# 19-CPLD.net
KiCad netlist of a schematic drawn in Altium Designer
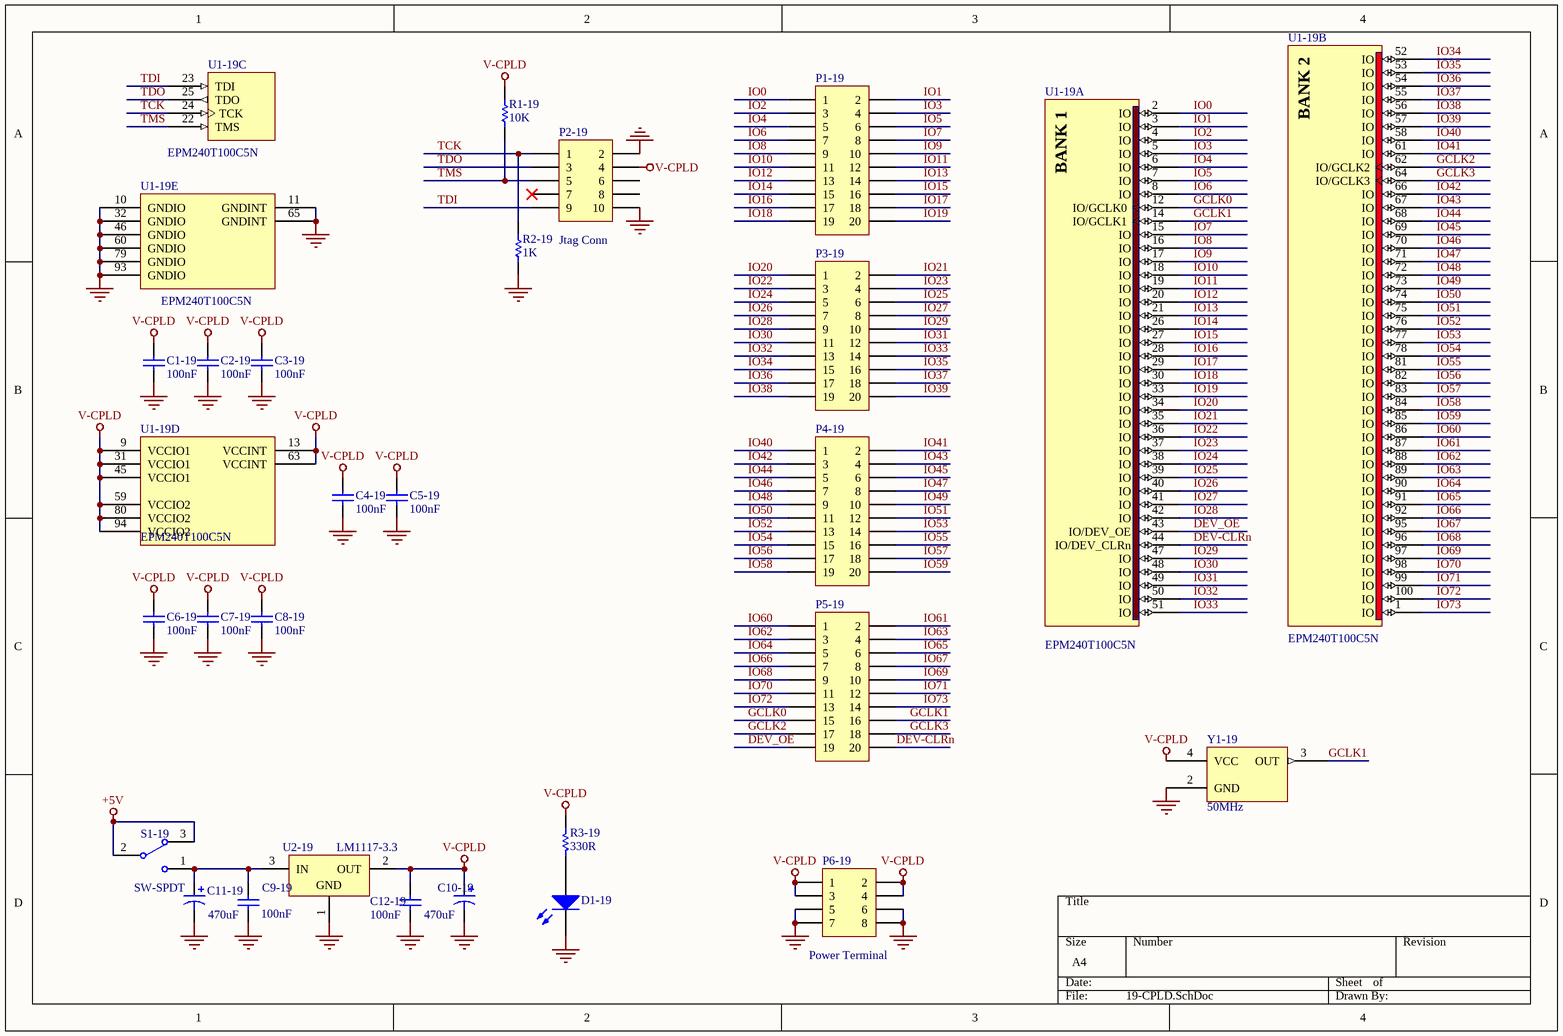
[diagram p0: 19-CPLD.SchDoc]

(export (version "E")
  (design (tool "Eeschema 10.0.6"))
  (components
    (comp (ref "C1-19")
      (value "100nF")
      (footprint "c-0805")
      (description "Capacitor")
      (fields (field (name "Comment") "104") (field (name "PUBLISHER") "Altium Limited"))
      (libsource (lib "Miscellaneous Devices") (part "Cap"))
    )
    (comp (ref "C2-19")
      (value "100nF")
      (footprint "c-0805")
      (description "Capacitor")
      (fields (field (name "Comment") "104") (field (name "PUBLISHER") "Altium Limited"))
      (libsource (lib "Miscellaneous Devices") (part "Cap"))
    )
    (comp (ref "C3-19")
      (value "100nF")
      (footprint "c-0805")
      (description "Capacitor")
      (fields (field (name "Comment") "104") (field (name "PUBLISHER") "Altium Limited"))
      (libsource (lib "Miscellaneous Devices") (part "Cap"))
    )
    (comp (ref "C4-19")
      (value "100nF")
      (footprint "c-0805")
      (description "Capacitor")
      (fields (field (name "Comment") "104") (field (name "PUBLISHER") "Altium Limited"))
      (libsource (lib "Miscellaneous Devices") (part "Cap"))
    )
    (comp (ref "C5-19")
      (value "100nF")
      (footprint "c-0805")
      (description "Capacitor")
      (fields (field (name "Comment") "104") (field (name "PUBLISHER") "Altium Limited"))
      (libsource (lib "Miscellaneous Devices") (part "Cap"))
    )
    (comp (ref "C6-19")
      (value "100nF")
      (footprint "c-0805")
      (description "Capacitor")
      (fields (field (name "Comment") "104") (field (name "PUBLISHER") "Altium Limited"))
      (libsource (lib "Miscellaneous Devices") (part "Cap"))
    )
    (comp (ref "C7-19")
      (value "100nF")
      (footprint "c-0805")
      (description "Capacitor")
      (fields (field (name "Comment") "104") (field (name "PUBLISHER") "Altium Limited"))
      (libsource (lib "Miscellaneous Devices") (part "Cap"))
    )
    (comp (ref "C8-19")
      (value "100nF")
      (footprint "c-0805")
      (description "Capacitor")
      (fields (field (name "Comment") "104") (field (name "PUBLISHER") "Altium Limited"))
      (libsource (lib "Miscellaneous Devices") (part "Cap"))
    )
    (comp (ref "C9-19")
      (value "100nF")
      (footprint "c-0805")
      (description "Capacitor")
      (fields
        (field (name "MANUFACTURER") "Generic Components")
        (field (name "Comment") "104")
        (field (name "PUBLISHER") "Altium Hobart Technology Centre")
      )
      (libsource (lib "Miscellaneous Devices") (part "Cap"))
    )
    (comp (ref "C10-19")
      (value "470uF")
      (footprint "C-ALU-10x10mm")
      (description "Polarized Capacitor (Radial)")
      (fields (field (name "Comment") "470uF/16V") (field (name "PUBLISHER") "Altium Limited"))
      (libsource (lib "Miscellaneous Devices") (part "Cap Pol1"))
    )
    (comp (ref "C11-19")
      (value "470uF")
      (footprint "C-ALU-10x10mm")
      (description "Polarized Capacitor (Radial)")
      (fields (field (name "Comment") "470uF/16V") (field (name "PUBLISHER") "Altium Limited"))
      (libsource (lib "Miscellaneous Devices") (part "Cap Pol1"))
    )
    (comp (ref "C12-19")
      (value "100nF")
      (footprint "c-0805")
      (description "Capacitor")
      (fields
        (field (name "MANUFACTURER") "Generic Components")
        (field (name "Comment") "104")
        (field (name "PUBLISHER") "Altium Hobart Technology Centre")
      )
      (libsource (lib "Miscellaneous Devices") (part "Cap"))
    )
    (comp (ref "D1-19")
      (value "LED")
      (footprint "LED-0805")
      (description "Typical INFRARED GaAs LED")
      (fields (field (name "PUBLISHER") "Altium Limited"))
      (libsource (lib "Miscellaneous Devices") (part "LED0"))
    )
    (comp (ref "P1-19")
      (value "H2")
      (footprint "HDR2X10")
      (description "Header, 10-Pin, Dual row")
      (libsource (lib "Miscellaneous Connectors") (part "Header 10X2"))
    )
    (comp (ref "P2-19")
      (value "Jtag Conn")
      (footprint "CONN-IDC-5X2-A")
      (description "Header, 5-Pin, Dual row")
      (fields (field (name "Comment") "IDE5x2"))
      (libsource (lib "Miscellaneous Connectors") (part "Header 5X2"))
    )
    (comp (ref "P3-19")
      (value "H2")
      (footprint "HDR2X10")
      (description "Header, 10-Pin, Dual row")
      (libsource (lib "Miscellaneous Connectors") (part "Header 10X2"))
    )
    (comp (ref "P4-19")
      (value "H2")
      (footprint "HDR2X10")
      (description "Header, 10-Pin, Dual row")
      (libsource (lib "Miscellaneous Connectors") (part "Header 10X2"))
    )
    (comp (ref "P5-19")
      (value "H2")
      (footprint "HDR2X10")
      (description "Header, 10-Pin, Dual row")
      (libsource (lib "Miscellaneous Connectors") (part "Header 10X2"))
    )
    (comp (ref "P6-19")
      (value "Header 4X2")
      (footprint "JP2.54-F-2x04A")
      (description "Header, 4-Pin, Dual row")
      (fields (field (name "PUBLISHER") "Power Terminal"))
      (libsource (lib "Miscellaneous Connectors") (part "Header 4X2"))
    )
    (comp (ref "R1-19")
      (value "10K")
      (footprint "R-0805")
      (description "Resistor")
      (fields (field (name "PUBLISHER") "Altium Limited"))
      (libsource (lib "Miscellaneous Devices") (part "Res1"))
    )
    (comp (ref "R2-19")
      (value "1K")
      (footprint "R-0805")
      (description "Resistor")
      (fields (field (name "PUBLISHER") "Altium Limited"))
      (libsource (lib "Miscellaneous Devices") (part "Res1"))
    )
    (comp (ref "R3-19")
      (value "330R")
      (footprint "R-0805")
      (description "Resistor")
      (fields (field (name "Comment") "331") (field (name "PUBLISHER") "Altium Limited"))
      (libsource (lib "") (part "Res1_1"))
    )
    (comp (ref "S1-19")
      (value "SW-SPDT")
      (footprint "SW-SLIDE-2P-2W")
      (description "SPDT Subminiature Toggle Switch, Right Angle Mounting, Vertical Actuation")
      (fields (field (name "PUBLISHER") "Altium Limited"))
      (libsource (lib "Miscellaneous Devices") (part "SW-SPDT"))
    )
    (comp (ref "U1-19")
      (value "EPM240T100C5N")
      (footprint "TQFP-100")
      (fields (field (name "PUBLISHER") "Altium Limited"))
      (libsource (lib "Altera MAX II") (part "EPM240T100C5N"))
    )
    (comp (ref "U2-19")
      (value "LM1117-3.3")
      (footprint "SOT-223-3")
      (description "800mA Low-Dropout Linear Regulator, 3-pin TO-252")
      (fields
        (field (name "PARTNUMBER") "LM1117IDTX-3.3")
        (field (name "MANUFACTURER") "National Semiconductor")
        (field (name "PUBLISHER") "Altium Limited")
      )
      (libsource (lib "NSC LDO") (part "LM1117IDTX-3.3"))
    )
    (comp (ref "Y1-19")
      (value "50MHz")
      (footprint "XTAL-SMD5070")
      (description "XTAL 50MHz, 4pin")
      (libsource (lib "Dlib") (part "OSC"))
    )
  )
  (nets
    (net (code "1") (name "+5V") (class "Default")
      (node (ref "S1-19") (pin "2") (pinfunction "2_2") (pintype "passive"))
      (node (ref "S1-19") (pin "3") (pinfunction "3_3") (pintype "passive"))
    )
    (net (code "2") (name "/DEV-CLRn") (class "Default")
      (node (ref "P5-19") (pin "20") (pinfunction "20_20") (pintype "passive"))
      (node (ref "U1-19") (pin "44") (pinfunction "IO/DEV_CLRn_44") (pintype "bidirectional"))
    )
    (net (code "3") (name "/DEV_OE") (class "Default")
      (node (ref "P5-19") (pin "19") (pinfunction "19_19") (pintype "passive"))
      (node (ref "U1-19") (pin "43") (pinfunction "IO/DEV_OE_43") (pintype "bidirectional"))
    )
    (net (code "4") (name "/GCLK0") (class "Default")
      (node (ref "P5-19") (pin "15") (pinfunction "15_15") (pintype "passive"))
      (node (ref "U1-19") (pin "12") (pinfunction "IO/GCLK0_12") (pintype "bidirectional"))
    )
    (net (code "5") (name "/GCLK1") (class "Default")
      (node (ref "P5-19") (pin "16") (pinfunction "16_16") (pintype "passive"))
      (node (ref "U1-19") (pin "14") (pinfunction "IO/GCLK1_14") (pintype "bidirectional"))
      (node (ref "Y1-19") (pin "3") (pinfunction "OUT_3") (pintype "output"))
    )
    (net (code "6") (name "/GCLK2") (class "Default")
      (node (ref "P5-19") (pin "17") (pinfunction "17_17") (pintype "passive"))
      (node (ref "U1-19") (pin "62") (pinfunction "IO/GCLK2_62") (pintype "bidirectional"))
    )
    (net (code "7") (name "/GCLK3") (class "Default")
      (node (ref "P5-19") (pin "18") (pinfunction "18_18") (pintype "passive"))
      (node (ref "U1-19") (pin "64") (pinfunction "IO/GCLK3_64") (pintype "bidirectional"))
    )
    (net (code "8") (name "/IO0") (class "Default")
      (node (ref "P1-19") (pin "1") (pinfunction "1_1") (pintype "passive"))
      (node (ref "U1-19") (pin "2") (pinfunction "IO_2") (pintype "bidirectional"))
    )
    (net (code "9") (name "/IO1") (class "Default")
      (node (ref "P1-19") (pin "2") (pinfunction "2_2") (pintype "passive"))
      (node (ref "U1-19") (pin "3") (pinfunction "IO_3") (pintype "bidirectional"))
    )
    (net (code "10") (name "/IO2") (class "Default")
      (node (ref "P1-19") (pin "3") (pinfunction "3_3") (pintype "passive"))
      (node (ref "U1-19") (pin "4") (pinfunction "IO_4") (pintype "bidirectional"))
    )
    (net (code "11") (name "/IO3") (class "Default")
      (node (ref "P1-19") (pin "4") (pinfunction "4_4") (pintype "passive"))
      (node (ref "U1-19") (pin "5") (pinfunction "IO_5") (pintype "bidirectional"))
    )
    (net (code "12") (name "/IO4") (class "Default")
      (node (ref "P1-19") (pin "5") (pinfunction "5_5") (pintype "passive"))
      (node (ref "U1-19") (pin "6") (pinfunction "IO_6") (pintype "bidirectional"))
    )
    (net (code "13") (name "/IO5") (class "Default")
      (node (ref "P1-19") (pin "6") (pinfunction "6_6") (pintype "passive"))
      (node (ref "U1-19") (pin "7") (pinfunction "IO_7") (pintype "bidirectional"))
    )
    (net (code "14") (name "/IO6") (class "Default")
      (node (ref "P1-19") (pin "7") (pinfunction "7_7") (pintype "passive"))
      (node (ref "U1-19") (pin "8") (pinfunction "IO_8") (pintype "bidirectional"))
    )
    (net (code "15") (name "/IO7") (class "Default")
      (node (ref "P1-19") (pin "8") (pinfunction "8_8") (pintype "passive"))
      (node (ref "U1-19") (pin "15") (pinfunction "IO_15") (pintype "bidirectional"))
    )
    (net (code "16") (name "/IO8") (class "Default")
      (node (ref "P1-19") (pin "9") (pinfunction "9_9") (pintype "passive"))
      (node (ref "U1-19") (pin "16") (pinfunction "IO_16") (pintype "bidirectional"))
    )
    (net (code "17") (name "/IO9") (class "Default")
      (node (ref "P1-19") (pin "10") (pinfunction "10_10") (pintype "passive"))
      (node (ref "U1-19") (pin "17") (pinfunction "IO_17") (pintype "bidirectional"))
    )
    (net (code "18") (name "/IO10") (class "Default")
      (node (ref "P1-19") (pin "11") (pinfunction "11_11") (pintype "passive"))
      (node (ref "U1-19") (pin "18") (pinfunction "IO_18") (pintype "bidirectional"))
    )
    (net (code "19") (name "/IO11") (class "Default")
      (node (ref "P1-19") (pin "12") (pinfunction "12_12") (pintype "passive"))
      (node (ref "U1-19") (pin "19") (pinfunction "IO_19") (pintype "bidirectional"))
    )
    (net (code "20") (name "/IO12") (class "Default")
      (node (ref "P1-19") (pin "13") (pinfunction "13_13") (pintype "passive"))
      (node (ref "U1-19") (pin "20") (pinfunction "IO_20") (pintype "bidirectional"))
    )
    (net (code "21") (name "/IO13") (class "Default")
      (node (ref "P1-19") (pin "14") (pinfunction "14_14") (pintype "passive"))
      (node (ref "U1-19") (pin "21") (pinfunction "IO_21") (pintype "bidirectional"))
    )
    (net (code "22") (name "/IO14") (class "Default")
      (node (ref "P1-19") (pin "15") (pinfunction "15_15") (pintype "passive"))
      (node (ref "U1-19") (pin "26") (pinfunction "IO_26") (pintype "bidirectional"))
    )
    (net (code "23") (name "/IO15") (class "Default")
      (node (ref "P1-19") (pin "16") (pinfunction "16_16") (pintype "passive"))
      (node (ref "U1-19") (pin "27") (pinfunction "IO_27") (pintype "bidirectional"))
    )
    (net (code "24") (name "/IO16") (class "Default")
      (node (ref "P1-19") (pin "17") (pinfunction "17_17") (pintype "passive"))
      (node (ref "U1-19") (pin "28") (pinfunction "IO_28") (pintype "bidirectional"))
    )
    (net (code "25") (name "/IO17") (class "Default")
      (node (ref "P1-19") (pin "18") (pinfunction "18_18") (pintype "passive"))
      (node (ref "U1-19") (pin "29") (pinfunction "IO_29") (pintype "bidirectional"))
    )
    (net (code "26") (name "/IO18") (class "Default")
      (node (ref "P1-19") (pin "19") (pinfunction "19_19") (pintype "passive"))
      (node (ref "U1-19") (pin "30") (pinfunction "IO_30") (pintype "bidirectional"))
    )
    (net (code "27") (name "/IO19") (class "Default")
      (node (ref "P1-19") (pin "20") (pinfunction "20_20") (pintype "passive"))
      (node (ref "U1-19") (pin "33") (pinfunction "IO_33") (pintype "bidirectional"))
    )
    (net (code "28") (name "/IO20") (class "Default")
      (node (ref "P3-19") (pin "1") (pinfunction "1_1") (pintype "passive"))
      (node (ref "U1-19") (pin "34") (pinfunction "IO_34") (pintype "bidirectional"))
    )
    (net (code "29") (name "/IO21") (class "Default")
      (node (ref "P3-19") (pin "2") (pinfunction "2_2") (pintype "passive"))
      (node (ref "U1-19") (pin "35") (pinfunction "IO_35") (pintype "bidirectional"))
    )
    (net (code "30") (name "/IO22") (class "Default")
      (node (ref "P3-19") (pin "3") (pinfunction "3_3") (pintype "passive"))
      (node (ref "U1-19") (pin "36") (pinfunction "IO_36") (pintype "bidirectional"))
    )
    (net (code "31") (name "/IO23") (class "Default")
      (node (ref "P3-19") (pin "4") (pinfunction "4_4") (pintype "passive"))
      (node (ref "U1-19") (pin "37") (pinfunction "IO_37") (pintype "bidirectional"))
    )
    (net (code "32") (name "/IO24") (class "Default")
      (node (ref "P3-19") (pin "5") (pinfunction "5_5") (pintype "passive"))
      (node (ref "U1-19") (pin "38") (pinfunction "IO_38") (pintype "bidirectional"))
    )
    (net (code "33") (name "/IO25") (class "Default")
      (node (ref "P3-19") (pin "6") (pinfunction "6_6") (pintype "passive"))
      (node (ref "U1-19") (pin "39") (pinfunction "IO_39") (pintype "bidirectional"))
    )
    (net (code "34") (name "/IO26") (class "Default")
      (node (ref "P3-19") (pin "7") (pinfunction "7_7") (pintype "passive"))
      (node (ref "U1-19") (pin "40") (pinfunction "IO_40") (pintype "bidirectional"))
    )
    (net (code "35") (name "/IO27") (class "Default")
      (node (ref "P3-19") (pin "8") (pinfunction "8_8") (pintype "passive"))
      (node (ref "U1-19") (pin "41") (pinfunction "IO_41") (pintype "bidirectional"))
    )
    (net (code "36") (name "/IO28") (class "Default")
      (node (ref "P3-19") (pin "9") (pinfunction "9_9") (pintype "passive"))
      (node (ref "U1-19") (pin "42") (pinfunction "IO_42") (pintype "bidirectional"))
    )
    (net (code "37") (name "/IO29") (class "Default")
      (node (ref "P3-19") (pin "10") (pinfunction "10_10") (pintype "passive"))
      (node (ref "U1-19") (pin "47") (pinfunction "IO_47") (pintype "bidirectional"))
    )
    (net (code "38") (name "/IO30") (class "Default")
      (node (ref "P3-19") (pin "11") (pinfunction "11_11") (pintype "passive"))
      (node (ref "U1-19") (pin "48") (pinfunction "IO_48") (pintype "bidirectional"))
    )
    (net (code "39") (name "/IO31") (class "Default")
      (node (ref "P3-19") (pin "12") (pinfunction "12_12") (pintype "passive"))
      (node (ref "U1-19") (pin "49") (pinfunction "IO_49") (pintype "bidirectional"))
    )
    (net (code "40") (name "/IO32") (class "Default")
      (node (ref "P3-19") (pin "13") (pinfunction "13_13") (pintype "passive"))
      (node (ref "U1-19") (pin "50") (pinfunction "IO_50") (pintype "bidirectional"))
    )
    (net (code "41") (name "/IO33") (class "Default")
      (node (ref "P3-19") (pin "14") (pinfunction "14_14") (pintype "passive"))
      (node (ref "U1-19") (pin "51") (pinfunction "IO_51") (pintype "bidirectional"))
    )
    (net (code "42") (name "/IO34") (class "Default")
      (node (ref "P3-19") (pin "15") (pinfunction "15_15") (pintype "passive"))
      (node (ref "U1-19") (pin "52") (pinfunction "IO_52") (pintype "bidirectional"))
    )
    (net (code "43") (name "/IO35") (class "Default")
      (node (ref "P3-19") (pin "16") (pinfunction "16_16") (pintype "passive"))
      (node (ref "U1-19") (pin "53") (pinfunction "IO_53") (pintype "bidirectional"))
    )
    (net (code "44") (name "/IO36") (class "Default")
      (node (ref "P3-19") (pin "17") (pinfunction "17_17") (pintype "passive"))
      (node (ref "U1-19") (pin "54") (pinfunction "IO_54") (pintype "bidirectional"))
    )
    (net (code "45") (name "/IO37") (class "Default")
      (node (ref "P3-19") (pin "18") (pinfunction "18_18") (pintype "passive"))
      (node (ref "U1-19") (pin "55") (pinfunction "IO_55") (pintype "bidirectional"))
    )
    (net (code "46") (name "/IO38") (class "Default")
      (node (ref "P3-19") (pin "19") (pinfunction "19_19") (pintype "passive"))
      (node (ref "U1-19") (pin "56") (pinfunction "IO_56") (pintype "bidirectional"))
    )
    (net (code "47") (name "/IO39") (class "Default")
      (node (ref "P3-19") (pin "20") (pinfunction "20_20") (pintype "passive"))
      (node (ref "U1-19") (pin "57") (pinfunction "IO_57") (pintype "bidirectional"))
    )
    (net (code "48") (name "/IO40") (class "Default")
      (node (ref "P4-19") (pin "1") (pinfunction "1_1") (pintype "passive"))
      (node (ref "U1-19") (pin "58") (pinfunction "IO_58") (pintype "bidirectional"))
    )
    (net (code "49") (name "/IO41") (class "Default")
      (node (ref "P4-19") (pin "2") (pinfunction "2_2") (pintype "passive"))
      (node (ref "U1-19") (pin "61") (pinfunction "IO_61") (pintype "bidirectional"))
    )
    (net (code "50") (name "/IO42") (class "Default")
      (node (ref "P4-19") (pin "3") (pinfunction "3_3") (pintype "passive"))
      (node (ref "U1-19") (pin "66") (pinfunction "IO_66") (pintype "bidirectional"))
    )
    (net (code "51") (name "/IO43") (class "Default")
      (node (ref "P4-19") (pin "4") (pinfunction "4_4") (pintype "passive"))
      (node (ref "U1-19") (pin "67") (pinfunction "IO_67") (pintype "bidirectional"))
    )
    (net (code "52") (name "/IO44") (class "Default")
      (node (ref "P4-19") (pin "5") (pinfunction "5_5") (pintype "passive"))
      (node (ref "U1-19") (pin "68") (pinfunction "IO_68") (pintype "bidirectional"))
    )
    (net (code "53") (name "/IO45") (class "Default")
      (node (ref "P4-19") (pin "6") (pinfunction "6_6") (pintype "passive"))
      (node (ref "U1-19") (pin "69") (pinfunction "IO_69") (pintype "bidirectional"))
    )
    (net (code "54") (name "/IO46") (class "Default")
      (node (ref "P4-19") (pin "7") (pinfunction "7_7") (pintype "passive"))
      (node (ref "U1-19") (pin "70") (pinfunction "IO_70") (pintype "bidirectional"))
    )
    (net (code "55") (name "/IO47") (class "Default")
      (node (ref "P4-19") (pin "8") (pinfunction "8_8") (pintype "passive"))
      (node (ref "U1-19") (pin "71") (pinfunction "IO_71") (pintype "bidirectional"))
    )
    (net (code "56") (name "/IO48") (class "Default")
      (node (ref "P4-19") (pin "9") (pinfunction "9_9") (pintype "passive"))
      (node (ref "U1-19") (pin "72") (pinfunction "IO_72") (pintype "bidirectional"))
    )
    (net (code "57") (name "/IO49") (class "Default")
      (node (ref "P4-19") (pin "10") (pinfunction "10_10") (pintype "passive"))
      (node (ref "U1-19") (pin "73") (pinfunction "IO_73") (pintype "bidirectional"))
    )
    (net (code "58") (name "/IO50") (class "Default")
      (node (ref "P4-19") (pin "11") (pinfunction "11_11") (pintype "passive"))
      (node (ref "U1-19") (pin "74") (pinfunction "IO_74") (pintype "bidirectional"))
    )
    (net (code "59") (name "/IO51") (class "Default")
      (node (ref "P4-19") (pin "12") (pinfunction "12_12") (pintype "passive"))
      (node (ref "U1-19") (pin "75") (pinfunction "IO_75") (pintype "bidirectional"))
    )
    (net (code "60") (name "/IO52") (class "Default")
      (node (ref "P4-19") (pin "13") (pinfunction "13_13") (pintype "passive"))
      (node (ref "U1-19") (pin "76") (pinfunction "IO_76") (pintype "bidirectional"))
    )
    (net (code "61") (name "/IO53") (class "Default")
      (node (ref "P4-19") (pin "14") (pinfunction "14_14") (pintype "passive"))
      (node (ref "U1-19") (pin "77") (pinfunction "IO_77") (pintype "bidirectional"))
    )
    (net (code "62") (name "/IO54") (class "Default")
      (node (ref "P4-19") (pin "15") (pinfunction "15_15") (pintype "passive"))
      (node (ref "U1-19") (pin "78") (pinfunction "IO_78") (pintype "bidirectional"))
    )
    (net (code "63") (name "/IO55") (class "Default")
      (node (ref "P4-19") (pin "16") (pinfunction "16_16") (pintype "passive"))
      (node (ref "U1-19") (pin "81") (pinfunction "IO_81") (pintype "bidirectional"))
    )
    (net (code "64") (name "/IO56") (class "Default")
      (node (ref "P4-19") (pin "17") (pinfunction "17_17") (pintype "passive"))
      (node (ref "U1-19") (pin "82") (pinfunction "IO_82") (pintype "bidirectional"))
    )
    (net (code "65") (name "/IO57") (class "Default")
      (node (ref "P4-19") (pin "18") (pinfunction "18_18") (pintype "passive"))
      (node (ref "U1-19") (pin "83") (pinfunction "IO_83") (pintype "bidirectional"))
    )
    (net (code "66") (name "/IO58") (class "Default")
      (node (ref "P4-19") (pin "19") (pinfunction "19_19") (pintype "passive"))
      (node (ref "U1-19") (pin "84") (pinfunction "IO_84") (pintype "bidirectional"))
    )
    (net (code "67") (name "/IO59") (class "Default")
      (node (ref "P4-19") (pin "20") (pinfunction "20_20") (pintype "passive"))
      (node (ref "U1-19") (pin "85") (pinfunction "IO_85") (pintype "bidirectional"))
    )
    (net (code "68") (name "/IO60") (class "Default")
      (node (ref "P5-19") (pin "1") (pinfunction "1_1") (pintype "passive"))
      (node (ref "U1-19") (pin "86") (pinfunction "IO_86") (pintype "bidirectional"))
    )
    (net (code "69") (name "/IO61") (class "Default")
      (node (ref "P5-19") (pin "2") (pinfunction "2_2") (pintype "passive"))
      (node (ref "U1-19") (pin "87") (pinfunction "IO_87") (pintype "bidirectional"))
    )
    (net (code "70") (name "/IO62") (class "Default")
      (node (ref "P5-19") (pin "3") (pinfunction "3_3") (pintype "passive"))
      (node (ref "U1-19") (pin "88") (pinfunction "IO_88") (pintype "bidirectional"))
    )
    (net (code "71") (name "/IO63") (class "Default")
      (node (ref "P5-19") (pin "4") (pinfunction "4_4") (pintype "passive"))
      (node (ref "U1-19") (pin "89") (pinfunction "IO_89") (pintype "bidirectional"))
    )
    (net (code "72") (name "/IO64") (class "Default")
      (node (ref "P5-19") (pin "5") (pinfunction "5_5") (pintype "passive"))
      (node (ref "U1-19") (pin "90") (pinfunction "IO_90") (pintype "bidirectional"))
    )
    (net (code "73") (name "/IO65") (class "Default")
      (node (ref "P5-19") (pin "6") (pinfunction "6_6") (pintype "passive"))
      (node (ref "U1-19") (pin "91") (pinfunction "IO_91") (pintype "bidirectional"))
    )
    (net (code "74") (name "/IO66") (class "Default")
      (node (ref "P5-19") (pin "7") (pinfunction "7_7") (pintype "passive"))
      (node (ref "U1-19") (pin "92") (pinfunction "IO_92") (pintype "bidirectional"))
    )
    (net (code "75") (name "/IO67") (class "Default")
      (node (ref "P5-19") (pin "8") (pinfunction "8_8") (pintype "passive"))
      (node (ref "U1-19") (pin "95") (pinfunction "IO_95") (pintype "bidirectional"))
    )
    (net (code "76") (name "/IO68") (class "Default")
      (node (ref "P5-19") (pin "9") (pinfunction "9_9") (pintype "passive"))
      (node (ref "U1-19") (pin "96") (pinfunction "IO_96") (pintype "bidirectional"))
    )
    (net (code "77") (name "/IO69") (class "Default")
      (node (ref "P5-19") (pin "10") (pinfunction "10_10") (pintype "passive"))
      (node (ref "U1-19") (pin "97") (pinfunction "IO_97") (pintype "bidirectional"))
    )
    (net (code "78") (name "/IO70") (class "Default")
      (node (ref "P5-19") (pin "11") (pinfunction "11_11") (pintype "passive"))
      (node (ref "U1-19") (pin "98") (pinfunction "IO_98") (pintype "bidirectional"))
    )
    (net (code "79") (name "/IO71") (class "Default")
      (node (ref "P5-19") (pin "12") (pinfunction "12_12") (pintype "passive"))
      (node (ref "U1-19") (pin "99") (pinfunction "IO_99") (pintype "bidirectional"))
    )
    (net (code "80") (name "/IO72") (class "Default")
      (node (ref "P5-19") (pin "13") (pinfunction "13_13") (pintype "passive"))
      (node (ref "U1-19") (pin "100") (pinfunction "IO_100") (pintype "bidirectional"))
    )
    (net (code "81") (name "/IO73") (class "Default")
      (node (ref "P5-19") (pin "14") (pinfunction "14_14") (pintype "passive"))
      (node (ref "U1-19") (pin "1") (pinfunction "IO_1") (pintype "bidirectional"))
    )
    (net (code "82") (name "/TCK") (class "Default")
      (node (ref "P2-19") (pin "1") (pinfunction "1_1") (pintype "passive"))
      (node (ref "R2-19") (pin "1") (pinfunction "1_1") (pintype "passive"))
      (node (ref "U1-19") (pin "24") (pinfunction "TCK_24") (pintype "input"))
    )
    (net (code "83") (name "/TDI") (class "Default")
      (node (ref "P2-19") (pin "9") (pinfunction "9_9") (pintype "passive"))
      (node (ref "U1-19") (pin "23") (pinfunction "TDI_23") (pintype "input"))
    )
    (net (code "84") (name "/TDO") (class "Default")
      (node (ref "P2-19") (pin "3") (pinfunction "3_3") (pintype "passive"))
      (node (ref "U1-19") (pin "25") (pinfunction "TDO_25") (pintype "output"))
    )
    (net (code "85") (name "/TMS") (class "Default")
      (node (ref "P2-19") (pin "5") (pinfunction "5_5") (pintype "passive"))
      (node (ref "R1-19") (pin "2") (pinfunction "2_2") (pintype "passive"))
      (node (ref "U1-19") (pin "22") (pinfunction "TMS_22") (pintype "input"))
    )
    (net (code "86") (name "GND") (class "Default")
      (node (ref "C1-19") (pin "2") (pinfunction "2_2") (pintype "passive"))
      (node (ref "C10-19") (pin "2") (pinfunction "2_2") (pintype "passive"))
      (node (ref "C11-19") (pin "2") (pinfunction "2_2") (pintype "passive"))
      (node (ref "C12-19") (pin "1") (pinfunction "1_1") (pintype "passive"))
      (node (ref "C2-19") (pin "2") (pinfunction "2_2") (pintype "passive"))
      (node (ref "C3-19") (pin "2") (pinfunction "2_2") (pintype "passive"))
      (node (ref "C4-19") (pin "2") (pinfunction "2_2") (pintype "passive"))
      (node (ref "C5-19") (pin "2") (pinfunction "2_2") (pintype "passive"))
      (node (ref "C6-19") (pin "2") (pinfunction "2_2") (pintype "passive"))
      (node (ref "C7-19") (pin "2") (pinfunction "2_2") (pintype "passive"))
      (node (ref "C8-19") (pin "2") (pinfunction "2_2") (pintype "passive"))
      (node (ref "C9-19") (pin "1") (pinfunction "1_1") (pintype "passive"))
      (node (ref "D1-19") (pin "2") (pinfunction "K_2") (pintype "passive"))
      (node (ref "P2-19") (pin "10") (pinfunction "10_10") (pintype "passive"))
      (node (ref "P2-19") (pin "2") (pinfunction "2_2") (pintype "passive"))
      (node (ref "P6-19") (pin "5") (pinfunction "5_5") (pintype "passive"))
      (node (ref "P6-19") (pin "6") (pinfunction "6_6") (pintype "passive"))
      (node (ref "P6-19") (pin "7") (pinfunction "7_7") (pintype "passive"))
      (node (ref "P6-19") (pin "8") (pinfunction "8_8") (pintype "passive"))
      (node (ref "R2-19") (pin "2") (pinfunction "2_2") (pintype "passive"))
      (node (ref "U1-19") (pin "10") (pinfunction "GNDIO_10") (pintype "power_in"))
      (node (ref "U1-19") (pin "11") (pinfunction "GNDINT_11") (pintype "power_in"))
      (node (ref "U1-19") (pin "32") (pinfunction "GNDIO_32") (pintype "power_in"))
      (node (ref "U1-19") (pin "46") (pinfunction "GNDIO_46") (pintype "power_in"))
      (node (ref "U1-19") (pin "60") (pinfunction "GNDIO_60") (pintype "power_in"))
      (node (ref "U1-19") (pin "65") (pinfunction "GNDINT_65") (pintype "power_in"))
      (node (ref "U1-19") (pin "79") (pinfunction "GNDIO_79") (pintype "power_in"))
      (node (ref "U1-19") (pin "93") (pinfunction "GNDIO_93") (pintype "power_in"))
      (node (ref "U2-19") (pin "1") (pinfunction "GND_1") (pintype "power_in"))
      (node (ref "Y1-19") (pin "2") (pinfunction "GND_2") (pintype "power_in"))
    )
    (net (code "87") (name "Net-(D1-19-A)") (class "Default")
      (node (ref "D1-19") (pin "1") (pinfunction "A_1") (pintype "passive"))
      (node (ref "R3-19") (pin "2") (pinfunction "2_2") (pintype "passive"))
    )
    (net (code "88") (name "Net-(U2-19-IN)") (class "Default")
      (node (ref "C11-19") (pin "1") (pinfunction "1_1") (pintype "passive"))
      (node (ref "C9-19") (pin "2") (pinfunction "2_2") (pintype "passive"))
      (node (ref "S1-19") (pin "1") (pinfunction "1_1") (pintype "passive"))
      (node (ref "U2-19") (pin "3") (pinfunction "IN_3") (pintype "power_in"))
    )
    (net (code "89") (name "V-CPLD") (class "Default")
      (node (ref "C1-19") (pin "1") (pinfunction "1_1") (pintype "passive"))
      (node (ref "C10-19") (pin "1") (pinfunction "1_1") (pintype "passive"))
      (node (ref "C12-19") (pin "2") (pinfunction "2_2") (pintype "passive"))
      (node (ref "C2-19") (pin "1") (pinfunction "1_1") (pintype "passive"))
      (node (ref "C3-19") (pin "1") (pinfunction "1_1") (pintype "passive"))
      (node (ref "C4-19") (pin "1") (pinfunction "1_1") (pintype "passive"))
      (node (ref "C5-19") (pin "1") (pinfunction "1_1") (pintype "passive"))
      (node (ref "C6-19") (pin "1") (pinfunction "1_1") (pintype "passive"))
      (node (ref "C7-19") (pin "1") (pinfunction "1_1") (pintype "passive"))
      (node (ref "C8-19") (pin "1") (pinfunction "1_1") (pintype "passive"))
      (node (ref "P2-19") (pin "4") (pinfunction "4_4") (pintype "passive"))
      (node (ref "P6-19") (pin "1") (pinfunction "1_1") (pintype "passive"))
      (node (ref "P6-19") (pin "2") (pinfunction "2_2") (pintype "passive"))
      (node (ref "P6-19") (pin "3") (pinfunction "3_3") (pintype "passive"))
      (node (ref "P6-19") (pin "4") (pinfunction "4_4") (pintype "passive"))
      (node (ref "R1-19") (pin "1") (pinfunction "1_1") (pintype "passive"))
      (node (ref "R3-19") (pin "1") (pinfunction "1_1") (pintype "passive"))
      (node (ref "U1-19") (pin "13") (pinfunction "VCCINT_13") (pintype "power_in"))
      (node (ref "U1-19") (pin "31") (pinfunction "VCCIO1_31") (pintype "power_in"))
      (node (ref "U1-19") (pin "45") (pinfunction "VCCIO1_45") (pintype "power_in"))
      (node (ref "U1-19") (pin "59") (pinfunction "VCCIO2_59") (pintype "power_in"))
      (node (ref "U1-19") (pin "63") (pinfunction "VCCINT_63") (pintype "power_in"))
      (node (ref "U1-19") (pin "80") (pinfunction "VCCIO2_80") (pintype "power_in"))
      (node (ref "U1-19") (pin "9") (pinfunction "VCCIO1_9") (pintype "power_in"))
      (node (ref "U1-19") (pin "94") (pinfunction "VCCIO2_94") (pintype "power_in"))
      (node (ref "U2-19") (pin "2") (pinfunction "OUT_2") (pintype "power_in"))
      (node (ref "Y1-19") (pin "4") (pinfunction "VCC_4") (pintype "power_in"))
    )
    (net (code "90") (name "unconnected-(P2-19-Pad6)") (class "Default")
      (node (ref "P2-19") (pin "6") (pinfunction "6_6") (pintype "passive"))
    )
    (net (code "91") (name "unconnected-(P2-19-Pad7)") (class "Default")
      (node (ref "P2-19") (pin "7") (pinfunction "7_7") (pintype "passive+no_connect"))
    )
    (net (code "92") (name "unconnected-(P2-19-Pad8)") (class "Default")
      (node (ref "P2-19") (pin "8") (pinfunction "8_8") (pintype "passive"))
    )
    (net (code "93") (name "unconnected-(Y1-19-NC-Pad1)") (class "Default")
      (node (ref "Y1-19") (pin "1") (pinfunction "NC_1") (pintype "passive"))
    )
  )
)
